# tdlf_16_02_2020_LED.net
KiCad netlist of a schematic drawn in EAGLE
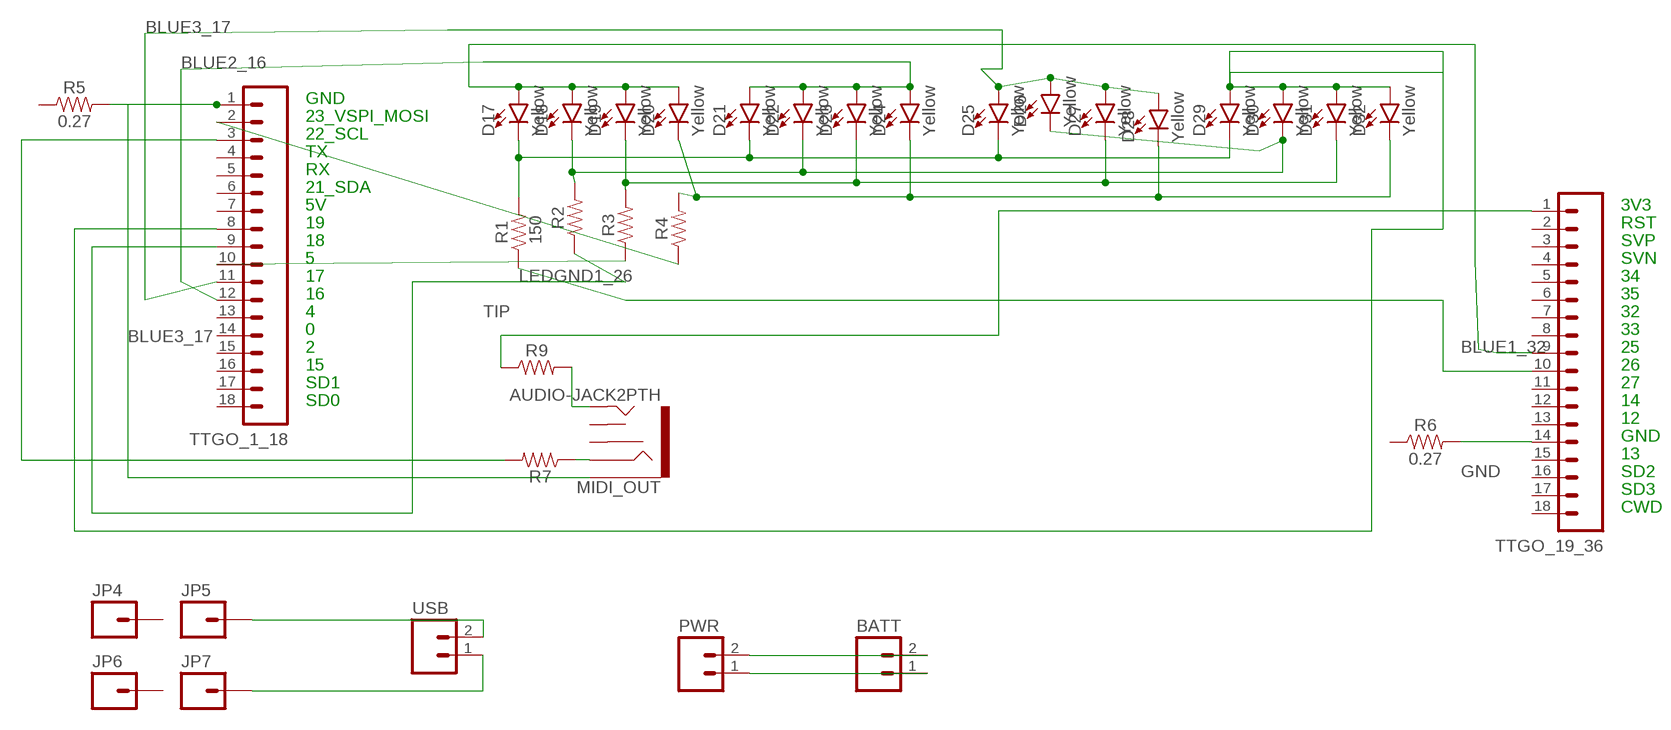
[diagram p0: schematic, sheet 1]

(export (version "E")
  (design (tool "Eeschema 10.0.6"))
  (components
    (comp (ref "BATT")
      (value "M02PTH")
      (footprint "eagle-import:1X02")
      (libsource (lib "eagle-import") (part "M02PTH"))
    )
    (comp (ref "D17")
      (value "Yellow")
      (footprint "eagle-import:LED-1206")
      (libsource (lib "eagle-import") (part "LED-YELLOWLILYPAD"))
    )
    (comp (ref "D18")
      (value "Yellow")
      (footprint "eagle-import:LED-1206")
      (libsource (lib "eagle-import") (part "LED-YELLOWLILYPAD"))
    )
    (comp (ref "D19")
      (value "Yellow")
      (footprint "eagle-import:LED-1206")
      (libsource (lib "eagle-import") (part "LED-YELLOWLILYPAD"))
    )
    (comp (ref "D20")
      (value "Yellow")
      (footprint "eagle-import:LED-1206")
      (libsource (lib "eagle-import") (part "LED-YELLOWLILYPAD"))
    )
    (comp (ref "D21")
      (value "Yellow")
      (footprint "eagle-import:LED-1206")
      (libsource (lib "eagle-import") (part "LED-YELLOWLILYPAD"))
    )
    (comp (ref "D22")
      (value "Yellow")
      (footprint "eagle-import:LED-1206")
      (libsource (lib "eagle-import") (part "LED-YELLOWLILYPAD"))
    )
    (comp (ref "D23")
      (value "Yellow")
      (footprint "eagle-import:LED-1206")
      (libsource (lib "eagle-import") (part "LED-YELLOWLILYPAD"))
    )
    (comp (ref "D24")
      (value "Yellow")
      (footprint "eagle-import:LED-1206")
      (libsource (lib "eagle-import") (part "LED-YELLOWLILYPAD"))
    )
    (comp (ref "D25")
      (value "Yellow")
      (footprint "eagle-import:LED-1206")
      (libsource (lib "eagle-import") (part "LED-YELLOWLILYPAD"))
    )
    (comp (ref "D26")
      (value "Yellow")
      (footprint "eagle-import:LED-1206")
      (libsource (lib "eagle-import") (part "LED-YELLOWLILYPAD"))
    )
    (comp (ref "D27")
      (value "Yellow")
      (footprint "eagle-import:LED-1206")
      (libsource (lib "eagle-import") (part "LED-YELLOWLILYPAD"))
    )
    (comp (ref "D28")
      (value "Yellow")
      (footprint "eagle-import:LED-1206")
      (libsource (lib "eagle-import") (part "LED-YELLOWLILYPAD"))
    )
    (comp (ref "D29")
      (value "Yellow")
      (footprint "eagle-import:LED-1206")
      (libsource (lib "eagle-import") (part "LED-YELLOWLILYPAD"))
    )
    (comp (ref "D30")
      (value "Yellow")
      (footprint "eagle-import:LED-1206")
      (libsource (lib "eagle-import") (part "LED-YELLOWLILYPAD"))
    )
    (comp (ref "D31")
      (value "Yellow")
      (footprint "eagle-import:LED-1206")
      (libsource (lib "eagle-import") (part "LED-YELLOWLILYPAD"))
    )
    (comp (ref "D32")
      (value "Yellow")
      (footprint "eagle-import:LED-1206")
      (libsource (lib "eagle-import") (part "LED-YELLOWLILYPAD"))
    )
    (comp (ref "JP4")
      (value "M01PTH")
      (footprint "eagle-import:1X01")
      (libsource (lib "eagle-import") (part "M01PTH"))
    )
    (comp (ref "JP5")
      (value "M01PTH")
      (footprint "eagle-import:1X01")
      (libsource (lib "eagle-import") (part "M01PTH"))
    )
    (comp (ref "JP6")
      (value "M01PTH")
      (footprint "eagle-import:1X01")
      (libsource (lib "eagle-import") (part "M01PTH"))
    )
    (comp (ref "JP7")
      (value "M01PTH")
      (footprint "eagle-import:1X01")
      (libsource (lib "eagle-import") (part "M01PTH"))
    )
    (comp (ref "MIDI_OUT")
      (value "AUDIO-JACK2PTH")
      (footprint "eagle-import:AUDIO-JACK")
      (libsource (lib "eagle-import") (part "AUDIO-JACK2PTH"))
    )
    (comp (ref "PWR")
      (value "M02PTH")
      (footprint "eagle-import:1X02")
      (libsource (lib "eagle-import") (part "M02PTH"))
    )
    (comp (ref "R1")
      (value "150")
      (footprint "eagle-import:1206")
      (libsource (lib "eagle-import") (part "RESISTOR1206"))
    )
    (comp (ref "R2")
      (value "RESISTOR1206")
      (footprint "eagle-import:1206")
      (libsource (lib "eagle-import") (part "RESISTOR1206"))
    )
    (comp (ref "R3")
      (value "RESISTOR1206")
      (footprint "eagle-import:1206")
      (libsource (lib "eagle-import") (part "RESISTOR1206"))
    )
    (comp (ref "R4")
      (value "RESISTOR1206")
      (footprint "eagle-import:1206")
      (libsource (lib "eagle-import") (part "RESISTOR1206"))
    )
    (comp (ref "R5")
      (value "0.27")
      (footprint "eagle-import:0603")
      (libsource (lib "eagle-import") (part "0.27OHM-0603-1/10W-1%"))
    )
    (comp (ref "R6")
      (value "0.27")
      (footprint "eagle-import:0603")
      (libsource (lib "eagle-import") (part "0.27OHM-0603-1/10W-1%"))
    )
    (comp (ref "R7")
      (value "RESISTOR1206")
      (footprint "eagle-import:1206")
      (libsource (lib "eagle-import") (part "RESISTOR1206"))
    )
    (comp (ref "R9")
      (value "RESISTOR1206")
      (footprint "eagle-import:1206")
      (libsource (lib "eagle-import") (part "RESISTOR1206"))
    )
    (comp (ref "TTGO_1_18")
      (value "M18_")
      (footprint "eagle-import:1X18")
      (libsource (lib "eagle-import") (part "M18_"))
    )
    (comp (ref "TTGO_19_36")
      (value "M18_")
      (footprint "eagle-import:1X18")
      (libsource (lib "eagle-import") (part "M18_"))
    )
    (comp (ref "USB")
      (value "M02PTH")
      (footprint "eagle-import:1X02")
      (libsource (lib "eagle-import") (part "M02PTH"))
    )
  )
  (nets
    (net (code "1") (name "/BLUE1_32") (class "Default")
      (node (ref "D17") (pin "A") (pinfunction "A_A") (pintype "passive"))
      (node (ref "D18") (pin "A") (pinfunction "A_A") (pintype "passive"))
      (node (ref "D19") (pin "A") (pinfunction "A_A") (pintype "passive"))
      (node (ref "D20") (pin "A") (pinfunction "A_A") (pintype "passive"))
      (node (ref "TTGO_19_36") (pin "9") (pinfunction "9_9") (pintype "passive"))
    )
    (net (code "2") (name "/BLUE2_16") (class "Default")
      (node (ref "D21") (pin "A") (pinfunction "A_A") (pintype "passive"))
      (node (ref "D22") (pin "A") (pinfunction "A_A") (pintype "passive"))
      (node (ref "D23") (pin "A") (pinfunction "A_A") (pintype "passive"))
      (node (ref "D24") (pin "A") (pinfunction "A_A") (pintype "passive"))
      (node (ref "TTGO_1_18") (pin "12") (pinfunction "12_12") (pintype "passive"))
    )
    (net (code "3") (name "/BLUE3_17") (class "Default")
      (node (ref "D25") (pin "A") (pinfunction "A_A") (pintype "passive"))
      (node (ref "D26") (pin "A") (pinfunction "A_A") (pintype "passive"))
      (node (ref "D27") (pin "A") (pinfunction "A_A") (pintype "passive"))
      (node (ref "D28") (pin "A") (pinfunction "A_A") (pintype "passive"))
      (node (ref "TTGO_1_18") (pin "11") (pinfunction "11_11") (pintype "passive"))
    )
    (net (code "4") (name "/GND") (class "Default")
      (node (ref "MIDI_OUT") (pin "SLEEVE") (pinfunction "SLEEVE_SLEEVE") (pintype "bidirectional"))
      (node (ref "R5") (pin "2") (pinfunction "2_2") (pintype "passive"))
      (node (ref "R6") (pin "2") (pinfunction "2_2") (pintype "passive"))
      (node (ref "TTGO_19_36") (pin "14") (pinfunction "14_14") (pintype "passive"))
      (node (ref "TTGO_1_18") (pin "1") (pinfunction "1_1") (pintype "passive"))
    )
    (net (code "5") (name "/LEDGND1_26") (class "Default")
      (node (ref "R1") (pin "1") (pinfunction "1_1") (pintype "passive"))
      (node (ref "TTGO_19_36") (pin "10") (pinfunction "10_10") (pintype "passive"))
    )
    (net (code "6") (name "/TIP") (class "Default")
      (node (ref "MIDI_OUT") (pin "TIP") (pinfunction "TIP_TIP") (pintype "bidirectional"))
      (node (ref "R9") (pin "2") (pinfunction "2_2") (pintype "passive"))
    )
    (net (code "7") (name "Net-(BATT-Pad1)") (class "Default")
      (node (ref "BATT") (pin "1") (pinfunction "1_1") (pintype "passive"))
      (node (ref "PWR") (pin "1") (pinfunction "1_1") (pintype "passive"))
    )
    (net (code "8") (name "Net-(BATT-Pad2)") (class "Default")
      (node (ref "BATT") (pin "2") (pinfunction "2_2") (pintype "passive"))
      (node (ref "PWR") (pin "2") (pinfunction "2_2") (pintype "passive"))
    )
    (net (code "9") (name "Net-(D17-PadC)") (class "Default")
      (node (ref "D17") (pin "C") (pinfunction "C_C") (pintype "passive"))
      (node (ref "D21") (pin "C") (pinfunction "C_C") (pintype "passive"))
      (node (ref "D25") (pin "C") (pinfunction "C_C") (pintype "passive"))
      (node (ref "D29") (pin "C") (pinfunction "C_C") (pintype "passive"))
      (node (ref "R1") (pin "2") (pinfunction "2_2") (pintype "passive"))
    )
    (net (code "10") (name "Net-(D18-PadC)") (class "Default")
      (node (ref "D18") (pin "C") (pinfunction "C_C") (pintype "passive"))
      (node (ref "D22") (pin "C") (pinfunction "C_C") (pintype "passive"))
      (node (ref "D26") (pin "C") (pinfunction "C_C") (pintype "passive"))
      (node (ref "D30") (pin "C") (pinfunction "C_C") (pintype "passive"))
      (node (ref "R2") (pin "2") (pinfunction "2_2") (pintype "passive"))
    )
    (net (code "11") (name "Net-(D19-PadC)") (class "Default")
      (node (ref "D19") (pin "C") (pinfunction "C_C") (pintype "passive"))
      (node (ref "D23") (pin "C") (pinfunction "C_C") (pintype "passive"))
      (node (ref "D27") (pin "C") (pinfunction "C_C") (pintype "passive"))
      (node (ref "D31") (pin "C") (pinfunction "C_C") (pintype "passive"))
      (node (ref "R3") (pin "2") (pinfunction "2_2") (pintype "passive"))
    )
    (net (code "12") (name "Net-(D20-PadC)") (class "Default")
      (node (ref "D20") (pin "C") (pinfunction "C_C") (pintype "passive"))
      (node (ref "D24") (pin "C") (pinfunction "C_C") (pintype "passive"))
      (node (ref "D28") (pin "C") (pinfunction "C_C") (pintype "passive"))
      (node (ref "D32") (pin "C") (pinfunction "C_C") (pintype "passive"))
      (node (ref "R4") (pin "2") (pinfunction "2_2") (pintype "passive"))
    )
    (net (code "13") (name "Net-(D29-PadA)") (class "Default")
      (node (ref "D29") (pin "A") (pinfunction "A_A") (pintype "passive"))
      (node (ref "D30") (pin "A") (pinfunction "A_A") (pintype "passive"))
      (node (ref "D31") (pin "A") (pinfunction "A_A") (pintype "passive"))
      (node (ref "D32") (pin "A") (pinfunction "A_A") (pintype "passive"))
      (node (ref "TTGO_1_18") (pin "8") (pinfunction "8_8") (pintype "passive"))
    )
    (net (code "14") (name "Net-(JP5-Pad1)") (class "Default")
      (node (ref "JP5") (pin "1") (pinfunction "1_1") (pintype "passive"))
      (node (ref "USB") (pin "2") (pinfunction "2_2") (pintype "passive"))
    )
    (net (code "15") (name "Net-(JP7-Pad1)") (class "Default")
      (node (ref "JP7") (pin "1") (pinfunction "1_1") (pintype "passive"))
      (node (ref "USB") (pin "1") (pinfunction "1_1") (pintype "passive"))
    )
    (net (code "16") (name "Net-(MIDI_OUT-PadRING)") (class "Default")
      (node (ref "MIDI_OUT") (pin "RING") (pinfunction "RING_RING") (pintype "bidirectional"))
      (node (ref "R7") (pin "1") (pinfunction "1_1") (pintype "passive"))
    )
    (net (code "17") (name "Net-(R2-Pad1)") (class "Default")
      (node (ref "R2") (pin "1") (pinfunction "1_1") (pintype "passive"))
      (node (ref "TTGO_1_18") (pin "9") (pinfunction "9_9") (pintype "passive"))
    )
    (net (code "18") (name "Net-(R3-Pad1)") (class "Default")
      (node (ref "R3") (pin "1") (pinfunction "1_1") (pintype "passive"))
      (node (ref "TTGO_1_18") (pin "10") (pinfunction "10_10") (pintype "passive"))
    )
    (net (code "19") (name "Net-(R4-Pad1)") (class "Default")
      (node (ref "R4") (pin "1") (pinfunction "1_1") (pintype "passive"))
      (node (ref "TTGO_1_18") (pin "2") (pinfunction "2_2") (pintype "passive"))
    )
    (net (code "20") (name "Net-(R7-Pad2)") (class "Default")
      (node (ref "R7") (pin "2") (pinfunction "2_2") (pintype "passive"))
      (node (ref "TTGO_1_18") (pin "3") (pinfunction "3_3") (pintype "passive"))
    )
    (net (code "21") (name "Net-(R9-Pad1)") (class "Default")
      (node (ref "R9") (pin "1") (pinfunction "1_1") (pintype "passive"))
      (node (ref "TTGO_19_36") (pin "1") (pinfunction "1_1") (pintype "passive"))
    )
    (net (code "22") (name "unconnected-(JP4-Pad1)") (class "Default")
      (node (ref "JP4") (pin "1") (pinfunction "1_1") (pintype "passive"))
    )
    (net (code "23") (name "unconnected-(JP6-Pad1)") (class "Default")
      (node (ref "JP6") (pin "1") (pinfunction "1_1") (pintype "passive"))
    )
    (net (code "24") (name "unconnected-(MIDI_OUT-PadRSH)") (class "Default")
      (node (ref "MIDI_OUT") (pin "RSH") (pinfunction "RSH_RSH") (pintype "bidirectional"))
    )
    (net (code "25") (name "unconnected-(MIDI_OUT-PadTSH)") (class "Default")
      (node (ref "MIDI_OUT") (pin "TSH") (pinfunction "TSH_TSH") (pintype "bidirectional"))
    )
    (net (code "26") (name "unconnected-(R5-Pad1)") (class "Default")
      (node (ref "R5") (pin "1") (pinfunction "1_1") (pintype "passive"))
    )
    (net (code "27") (name "unconnected-(R6-Pad1)") (class "Default")
      (node (ref "R6") (pin "1") (pinfunction "1_1") (pintype "passive"))
    )
    (net (code "28") (name "unconnected-(TTGO_1_18-Pad4)") (class "Default")
      (node (ref "TTGO_1_18") (pin "4") (pinfunction "4_4") (pintype "passive"))
    )
    (net (code "29") (name "unconnected-(TTGO_1_18-Pad5)") (class "Default")
      (node (ref "TTGO_1_18") (pin "5") (pinfunction "5_5") (pintype "passive"))
    )
    (net (code "30") (name "unconnected-(TTGO_1_18-Pad6)") (class "Default")
      (node (ref "TTGO_1_18") (pin "6") (pinfunction "6_6") (pintype "passive"))
    )
    (net (code "31") (name "unconnected-(TTGO_1_18-Pad7)") (class "Default")
      (node (ref "TTGO_1_18") (pin "7") (pinfunction "7_7") (pintype "passive"))
    )
    (net (code "32") (name "unconnected-(TTGO_1_18-Pad13)") (class "Default")
      (node (ref "TTGO_1_18") (pin "13") (pinfunction "13_13") (pintype "passive"))
    )
    (net (code "33") (name "unconnected-(TTGO_1_18-Pad14)") (class "Default")
      (node (ref "TTGO_1_18") (pin "14") (pinfunction "14_14") (pintype "passive"))
    )
    (net (code "34") (name "unconnected-(TTGO_1_18-Pad15)") (class "Default")
      (node (ref "TTGO_1_18") (pin "15") (pinfunction "15_15") (pintype "passive"))
    )
    (net (code "35") (name "unconnected-(TTGO_1_18-Pad16)") (class "Default")
      (node (ref "TTGO_1_18") (pin "16") (pinfunction "16_16") (pintype "passive"))
    )
    (net (code "36") (name "unconnected-(TTGO_1_18-Pad17)") (class "Default")
      (node (ref "TTGO_1_18") (pin "17") (pinfunction "17_17") (pintype "passive"))
    )
    (net (code "37") (name "unconnected-(TTGO_1_18-Pad18)") (class "Default")
      (node (ref "TTGO_1_18") (pin "18") (pinfunction "18_18") (pintype "passive"))
    )
    (net (code "38") (name "unconnected-(TTGO_19_36-Pad2)") (class "Default")
      (node (ref "TTGO_19_36") (pin "2") (pinfunction "2_2") (pintype "passive"))
    )
    (net (code "39") (name "unconnected-(TTGO_19_36-Pad3)") (class "Default")
      (node (ref "TTGO_19_36") (pin "3") (pinfunction "3_3") (pintype "passive"))
    )
    (net (code "40") (name "unconnected-(TTGO_19_36-Pad4)") (class "Default")
      (node (ref "TTGO_19_36") (pin "4") (pinfunction "4_4") (pintype "passive"))
    )
    (net (code "41") (name "unconnected-(TTGO_19_36-Pad5)") (class "Default")
      (node (ref "TTGO_19_36") (pin "5") (pinfunction "5_5") (pintype "passive"))
    )
    (net (code "42") (name "unconnected-(TTGO_19_36-Pad6)") (class "Default")
      (node (ref "TTGO_19_36") (pin "6") (pinfunction "6_6") (pintype "passive"))
    )
    (net (code "43") (name "unconnected-(TTGO_19_36-Pad7)") (class "Default")
      (node (ref "TTGO_19_36") (pin "7") (pinfunction "7_7") (pintype "passive"))
    )
    (net (code "44") (name "unconnected-(TTGO_19_36-Pad8)") (class "Default")
      (node (ref "TTGO_19_36") (pin "8") (pinfunction "8_8") (pintype "passive"))
    )
    (net (code "45") (name "unconnected-(TTGO_19_36-Pad11)") (class "Default")
      (node (ref "TTGO_19_36") (pin "11") (pinfunction "11_11") (pintype "passive"))
    )
    (net (code "46") (name "unconnected-(TTGO_19_36-Pad12)") (class "Default")
      (node (ref "TTGO_19_36") (pin "12") (pinfunction "12_12") (pintype "passive"))
    )
    (net (code "47") (name "unconnected-(TTGO_19_36-Pad13)") (class "Default")
      (node (ref "TTGO_19_36") (pin "13") (pinfunction "13_13") (pintype "passive"))
    )
    (net (code "48") (name "unconnected-(TTGO_19_36-Pad15)") (class "Default")
      (node (ref "TTGO_19_36") (pin "15") (pinfunction "15_15") (pintype "passive"))
    )
    (net (code "49") (name "unconnected-(TTGO_19_36-Pad16)") (class "Default")
      (node (ref "TTGO_19_36") (pin "16") (pinfunction "16_16") (pintype "passive"))
    )
    (net (code "50") (name "unconnected-(TTGO_19_36-Pad17)") (class "Default")
      (node (ref "TTGO_19_36") (pin "17") (pinfunction "17_17") (pintype "passive"))
    )
    (net (code "51") (name "unconnected-(TTGO_19_36-Pad18)") (class "Default")
      (node (ref "TTGO_19_36") (pin "18") (pinfunction "18_18") (pintype "passive"))
    )
  )
)
